# radio_v2.net
KiCad netlist of a schematic drawn in EAGLE
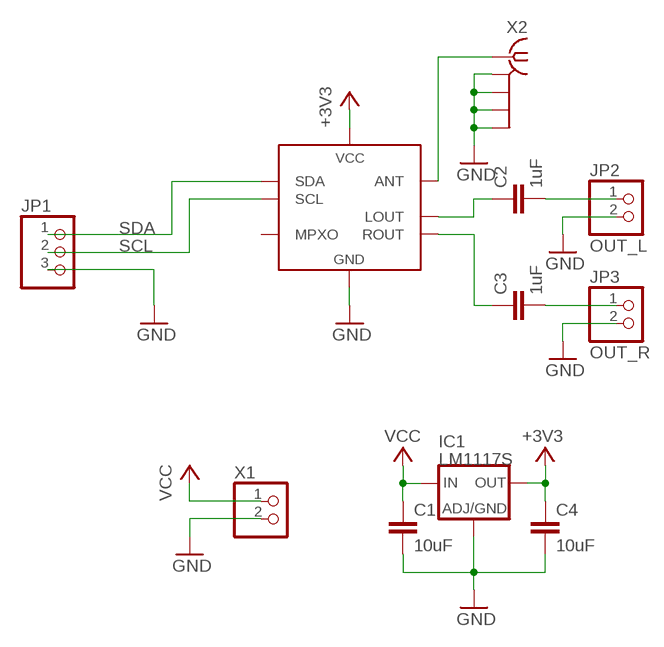
[diagram p0: schematic, sheet 1]

(export (version "E")
  (design (tool "Eeschema 10.0.6"))
  (components
    (comp (ref "C1")
      (value "10uF")
      (footprint "eagle-import:C0805K")
      (libsource (lib "eagle-import") (part "C-EUC0805K"))
    )
    (comp (ref "C2")
      (value "1uF")
      (footprint "eagle-import:C0805K")
      (libsource (lib "eagle-import") (part "C-EUC0805K"))
    )
    (comp (ref "C3")
      (value "1uF")
      (footprint "eagle-import:C0805K")
      (libsource (lib "eagle-import") (part "C-EUC0805K"))
    )
    (comp (ref "C4")
      (value "10uF")
      (footprint "eagle-import:C0805K")
      (libsource (lib "eagle-import") (part "C-EUC0805K"))
    )
    (comp (ref "IC1")
      (value "LM1117S")
      (footprint "eagle-import:SOT223")
      (libsource (lib "eagle-import") (part "LM1117S"))
    )
    (comp (ref "JP1")
      (value "PINHD-1X3180")
      (footprint "eagle-import:1X03")
      (libsource (lib "eagle-import") (part "PINHD-1X3180"))
    )
    (comp (ref "JP2")
      (value "OUT_L")
      (footprint "eagle-import:1X02")
      (libsource (lib "eagle-import") (part "PINHD-1X2"))
    )
    (comp (ref "JP3")
      (value "OUT_R")
      (footprint "eagle-import:1X02")
      (libsource (lib "eagle-import") (part "PINHD-1X2"))
    )
    (comp (ref "U1")
      (value "TEA5767")
      (footprint "eagle-import:TEA5767")
      (libsource (lib "eagle-import") (part "TEA5767"))
    )
    (comp (ref "X1")
      (value "22-23-2021")
      (footprint "eagle-import:22-23-2021")
      (libsource (lib "eagle-import") (part "22-23-2021"))
    )
    (comp (ref "X2")
      (value "BU-SMA-V")
      (footprint "eagle-import:BU-SMA-V")
      (libsource (lib "eagle-import") (part "BU-SMA-V"))
    )
  )
  (nets
    (net (code "1") (name "+3V3") (class "Default")
      (node (ref "C4") (pin "1") (pinfunction "1_1") (pintype "passive"))
      (node (ref "IC1") (pin "2") (pinfunction "OUT_2") (pintype "passive"))
      (node (ref "IC1") (pin "4") (pinfunction "OUT_4") (pintype "passive"))
      (node (ref "U1") (pin "5") (pinfunction "VCC_5") (pintype "bidirectional"))
    )
    (net (code "2") (name "/SCL") (class "Default")
      (node (ref "JP1") (pin "2") (pinfunction "2_2") (pintype "passive"))
      (node (ref "U1") (pin "2") (pinfunction "SCL_2") (pintype "bidirectional"))
    )
    (net (code "3") (name "/SDA") (class "Default")
      (node (ref "JP1") (pin "1") (pinfunction "1_1") (pintype "passive"))
      (node (ref "U1") (pin "1") (pinfunction "SDA_1") (pintype "bidirectional"))
    )
    (net (code "4") (name "GND") (class "Default")
      (node (ref "C1") (pin "2") (pinfunction "2_2") (pintype "passive"))
      (node (ref "C4") (pin "2") (pinfunction "2_2") (pintype "passive"))
      (node (ref "IC1") (pin "1") (pinfunction "ADJ_1") (pintype "input"))
      (node (ref "JP1") (pin "3") (pinfunction "3_3") (pintype "passive"))
      (node (ref "JP2") (pin "2") (pinfunction "2_2") (pintype "passive"))
      (node (ref "JP3") (pin "2") (pinfunction "2_2") (pintype "passive"))
      (node (ref "U1") (pin "3") (pinfunction "GND_3") (pintype "bidirectional"))
      (node (ref "U1") (pin "6") (pinfunction "GND_6") (pintype "bidirectional"))
      (node (ref "X1") (pin "2") (pinfunction "2_2") (pintype "passive"))
      (node (ref "X2") (pin "2") (pinfunction "GND1_2") (pintype "power_in"))
      (node (ref "X2") (pin "3") (pinfunction "GND2_3") (pintype "power_in"))
      (node (ref "X2") (pin "4") (pinfunction "GND3_4") (pintype "power_in"))
      (node (ref "X2") (pin "5") (pinfunction "GND4_5") (pintype "power_in"))
    )
    (net (code "5") (name "Net-(C2-Pad2)") (class "Default")
      (node (ref "C2") (pin "2") (pinfunction "2_2") (pintype "passive"))
      (node (ref "JP2") (pin "1") (pinfunction "1_1") (pintype "passive"))
    )
    (net (code "6") (name "Net-(C3-Pad2)") (class "Default")
      (node (ref "C3") (pin "2") (pinfunction "2_2") (pintype "passive"))
      (node (ref "JP3") (pin "1") (pinfunction "1_1") (pintype "passive"))
    )
    (net (code "7") (name "Net-(U1-ANT)") (class "Default")
      (node (ref "U1") (pin "10") (pinfunction "ANT_10") (pintype "bidirectional"))
      (node (ref "X2") (pin "1") (pinfunction "1_1") (pintype "passive"))
    )
    (net (code "8") (name "Net-(U1-LOUT)") (class "Default")
      (node (ref "C2") (pin "1") (pinfunction "1_1") (pintype "passive"))
      (node (ref "U1") (pin "8") (pinfunction "LOUT_8") (pintype "bidirectional"))
    )
    (net (code "9") (name "Net-(U1-ROUT)") (class "Default")
      (node (ref "C3") (pin "1") (pinfunction "1_1") (pintype "passive"))
      (node (ref "U1") (pin "7") (pinfunction "ROUT_7") (pintype "bidirectional"))
    )
    (net (code "10") (name "VCC") (class "Default")
      (node (ref "C1") (pin "1") (pinfunction "1_1") (pintype "passive"))
      (node (ref "IC1") (pin "3") (pinfunction "IN_3") (pintype "input"))
      (node (ref "X1") (pin "1") (pinfunction "1_1") (pintype "passive"))
    )
    (net (code "11") (name "unconnected-(U1-MPXO-Pad9)") (class "Default")
      (node (ref "U1") (pin "9") (pinfunction "MPXO_9") (pintype "bidirectional"))
    )
  )
)
